# FMC_HPC_400.net
KiCad netlist of a schematic drawn in Altium Designer
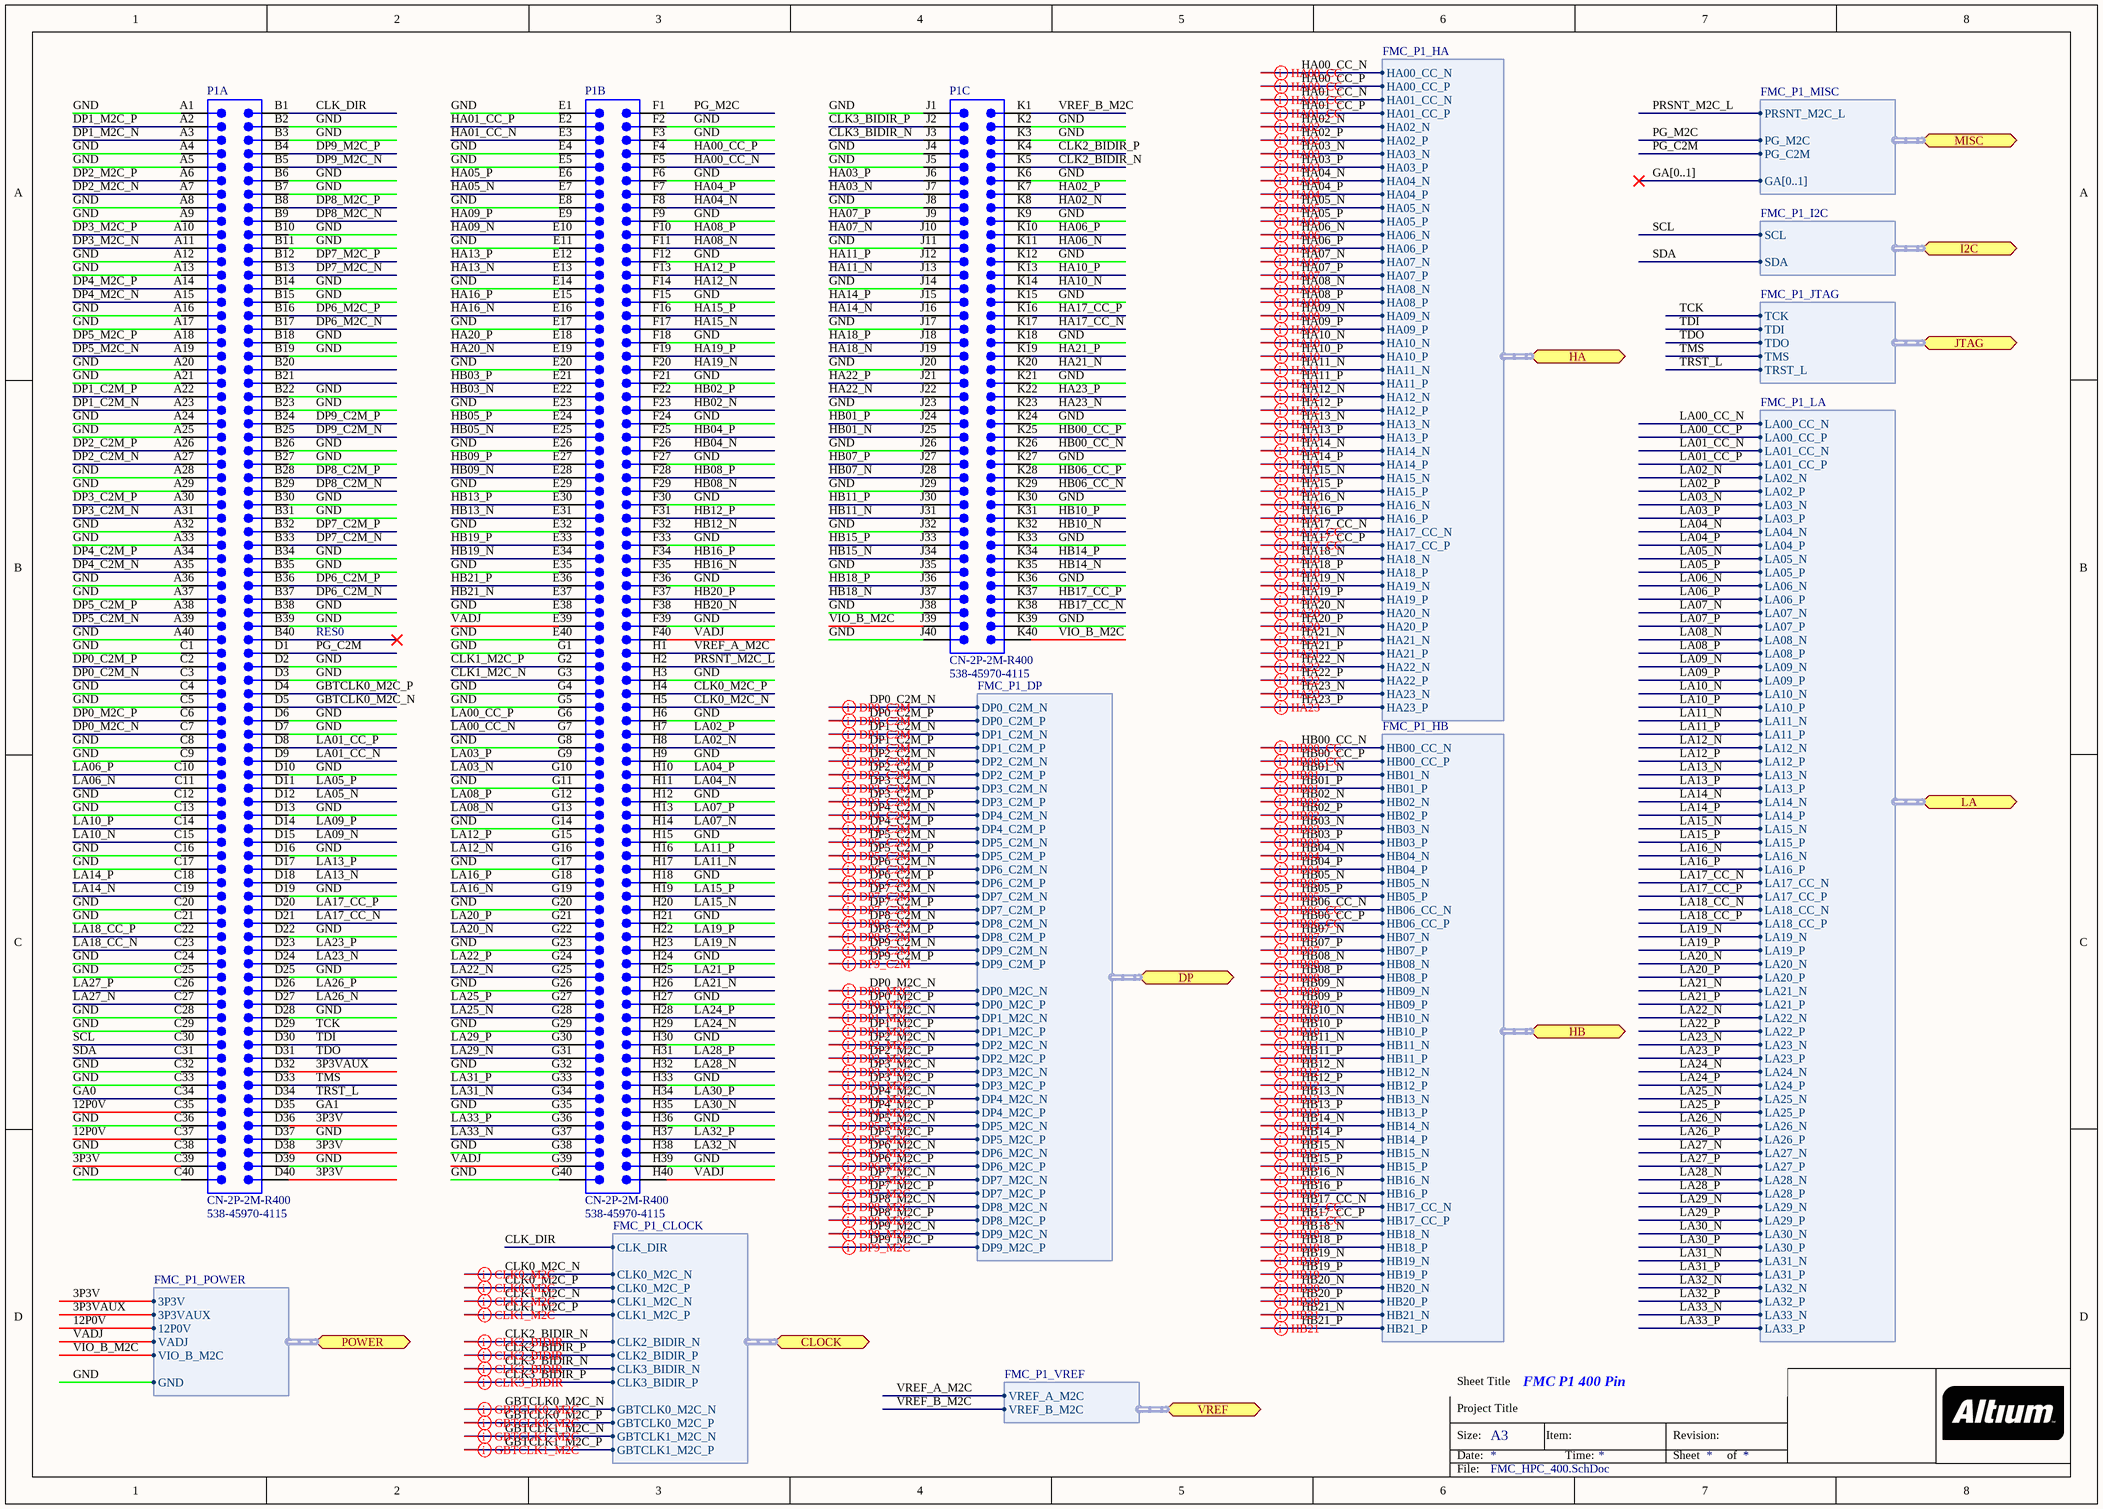
[diagram p0: FMC_HPC_400.SchDoc]

(export (version "E")
  (design (tool "Eeschema 10.0.6"))
  (components
    (comp (ref "P1")
      (value "CN-2P-2M-R400")
      (footprint "BTB-SM1-27-2V400M")
      (description "Board-to-Board Connector, Vertical, 10-Row, Pitch 1.27mm, 400-Position")
      (fields
        (field (name "MANUFACTURER") "Molex")
        (field (name "MANUFACTURER PART NUMBER") "45970-4115")
        (field (name "SUPPLIER PART NUMBER 1") "538-45970-4115")
      )
      (libsource (lib "RNG_Parts") (part "CN-2P-2M-R400"))
    )
  )
  (nets
    (net (code "11") (name "/3P3V") (class "Default")
      (node (ref "P1") (pin "C39") (pinfunction "C39_C39") (pintype "passive"))
      (node (ref "P1") (pin "D36") (pinfunction "D36_D36") (pintype "passive"))
      (node (ref "P1") (pin "D38") (pinfunction "D38_D38") (pintype "passive"))
      (node (ref "P1") (pin "D40") (pinfunction "D40_D40") (pintype "passive"))
    )
    (net (code "12") (name "/3P3VAUX") (class "Default")
      (node (ref "P1") (pin "D32") (pinfunction "D32_D32") (pintype "passive"))
    )
    (net (code "13") (name "/12P0V") (class "Default")
      (node (ref "P1") (pin "C35") (pinfunction "C35_C35") (pintype "passive"))
      (node (ref "P1") (pin "C37") (pinfunction "C37_C37") (pintype "passive"))
    )
    (net (code "14") (name "/CLK0_M2C_N") (class "Default")
      (node (ref "P1") (pin "H5") (pinfunction "H5_H5") (pintype "passive"))
    )
    (net (code "15") (name "/CLK0_M2C_P") (class "Default")
      (node (ref "P1") (pin "H4") (pinfunction "H4_H4") (pintype "passive"))
    )
    (net (code "16") (name "/CLK1_M2C_N") (class "Default")
      (node (ref "P1") (pin "G3") (pinfunction "G3_G3") (pintype "passive"))
    )
    (net (code "17") (name "/CLK1_M2C_P") (class "Default")
      (node (ref "P1") (pin "G2") (pinfunction "G2_G2") (pintype "passive"))
    )
    (net (code "18") (name "/CLK2_BIDIR_N") (class "Default")
      (node (ref "P1") (pin "K5") (pinfunction "K5_K5") (pintype "passive"))
    )
    (net (code "19") (name "/CLK2_BIDIR_P") (class "Default")
      (node (ref "P1") (pin "K4") (pinfunction "K4_K4") (pintype "passive"))
    )
    (net (code "20") (name "/CLK3_BIDIR_N") (class "Default")
      (node (ref "P1") (pin "J3") (pinfunction "J3_J3") (pintype "passive"))
    )
    (net (code "21") (name "/CLK3_BIDIR_P") (class "Default")
      (node (ref "P1") (pin "J2") (pinfunction "J2_J2") (pintype "passive"))
    )
    (net (code "22") (name "/CLK_DIR") (class "Default")
      (node (ref "P1") (pin "B1") (pinfunction "B1_B1") (pintype "passive"))
    )
    (net (code "23") (name "/DP0_C2M_N") (class "Default")
      (node (ref "P1") (pin "C3") (pinfunction "C3_C3") (pintype "passive"))
    )
    (net (code "24") (name "/DP0_C2M_P") (class "Default")
      (node (ref "P1") (pin "C2") (pinfunction "C2_C2") (pintype "passive"))
    )
    (net (code "25") (name "/DP0_M2C_N") (class "Default")
      (node (ref "P1") (pin "C7") (pinfunction "C7_C7") (pintype "passive"))
    )
    (net (code "26") (name "/DP0_M2C_P") (class "Default")
      (node (ref "P1") (pin "C6") (pinfunction "C6_C6") (pintype "passive"))
    )
    (net (code "27") (name "/DP1_C2M_N") (class "Default")
      (node (ref "P1") (pin "A23") (pinfunction "A23_A23") (pintype "passive"))
    )
    (net (code "28") (name "/DP1_C2M_P") (class "Default")
      (node (ref "P1") (pin "A22") (pinfunction "A22_A22") (pintype "passive"))
    )
    (net (code "29") (name "/DP1_M2C_N") (class "Default")
      (node (ref "P1") (pin "A3") (pinfunction "A3_A3") (pintype "passive"))
    )
    (net (code "30") (name "/DP1_M2C_P") (class "Default")
      (node (ref "P1") (pin "A2") (pinfunction "A2_A2") (pintype "passive"))
    )
    (net (code "31") (name "/DP2_C2M_N") (class "Default")
      (node (ref "P1") (pin "A27") (pinfunction "A27_A27") (pintype "passive"))
    )
    (net (code "32") (name "/DP2_C2M_P") (class "Default")
      (node (ref "P1") (pin "A26") (pinfunction "A26_A26") (pintype "passive"))
    )
    (net (code "33") (name "/DP2_M2C_N") (class "Default")
      (node (ref "P1") (pin "A7") (pinfunction "A7_A7") (pintype "passive"))
    )
    (net (code "34") (name "/DP2_M2C_P") (class "Default")
      (node (ref "P1") (pin "A6") (pinfunction "A6_A6") (pintype "passive"))
    )
    (net (code "35") (name "/DP3_C2M_N") (class "Default")
      (node (ref "P1") (pin "A31") (pinfunction "A31_A31") (pintype "passive"))
    )
    (net (code "36") (name "/DP3_C2M_P") (class "Default")
      (node (ref "P1") (pin "A30") (pinfunction "A30_A30") (pintype "passive"))
    )
    (net (code "37") (name "/DP3_M2C_N") (class "Default")
      (node (ref "P1") (pin "A11") (pinfunction "A11_A11") (pintype "passive"))
    )
    (net (code "38") (name "/DP3_M2C_P") (class "Default")
      (node (ref "P1") (pin "A10") (pinfunction "A10_A10") (pintype "passive"))
    )
    (net (code "39") (name "/DP4_C2M_N") (class "Default")
      (node (ref "P1") (pin "A35") (pinfunction "A35_A35") (pintype "passive"))
    )
    (net (code "40") (name "/DP4_C2M_P") (class "Default")
      (node (ref "P1") (pin "A34") (pinfunction "A34_A34") (pintype "passive"))
    )
    (net (code "41") (name "/DP4_M2C_N") (class "Default")
      (node (ref "P1") (pin "A15") (pinfunction "A15_A15") (pintype "passive"))
    )
    (net (code "42") (name "/DP4_M2C_P") (class "Default")
      (node (ref "P1") (pin "A14") (pinfunction "A14_A14") (pintype "passive"))
    )
    (net (code "43") (name "/DP5_C2M_N") (class "Default")
      (node (ref "P1") (pin "A39") (pinfunction "A39_A39") (pintype "passive"))
    )
    (net (code "44") (name "/DP5_C2M_P") (class "Default")
      (node (ref "P1") (pin "A38") (pinfunction "A38_A38") (pintype "passive"))
    )
    (net (code "45") (name "/DP5_M2C_N") (class "Default")
      (node (ref "P1") (pin "A19") (pinfunction "A19_A19") (pintype "passive"))
    )
    (net (code "46") (name "/DP5_M2C_P") (class "Default")
      (node (ref "P1") (pin "A18") (pinfunction "A18_A18") (pintype "passive"))
    )
    (net (code "47") (name "/DP6_C2M_N") (class "Default")
      (node (ref "P1") (pin "B37") (pinfunction "B37_B37") (pintype "passive"))
    )
    (net (code "48") (name "/DP6_C2M_P") (class "Default")
      (node (ref "P1") (pin "B36") (pinfunction "B36_B36") (pintype "passive"))
    )
    (net (code "49") (name "/DP6_M2C_N") (class "Default")
      (node (ref "P1") (pin "B17") (pinfunction "B17_B17") (pintype "passive"))
    )
    (net (code "50") (name "/DP6_M2C_P") (class "Default")
      (node (ref "P1") (pin "B16") (pinfunction "B16_B16") (pintype "passive"))
    )
    (net (code "51") (name "/DP7_C2M_N") (class "Default")
      (node (ref "P1") (pin "B33") (pinfunction "B33_B33") (pintype "passive"))
    )
    (net (code "52") (name "/DP7_C2M_P") (class "Default")
      (node (ref "P1") (pin "B32") (pinfunction "B32_B32") (pintype "passive"))
    )
    (net (code "53") (name "/DP7_M2C_N") (class "Default")
      (node (ref "P1") (pin "B13") (pinfunction "B13_B13") (pintype "passive"))
    )
    (net (code "54") (name "/DP7_M2C_P") (class "Default")
      (node (ref "P1") (pin "B12") (pinfunction "B12_B12") (pintype "passive"))
    )
    (net (code "55") (name "/DP8_C2M_N") (class "Default")
      (node (ref "P1") (pin "B29") (pinfunction "B29_B29") (pintype "passive"))
    )
    (net (code "56") (name "/DP8_C2M_P") (class "Default")
      (node (ref "P1") (pin "B28") (pinfunction "B28_B28") (pintype "passive"))
    )
    (net (code "57") (name "/DP8_M2C_N") (class "Default")
      (node (ref "P1") (pin "B9") (pinfunction "B9_B9") (pintype "passive"))
    )
    (net (code "58") (name "/DP8_M2C_P") (class "Default")
      (node (ref "P1") (pin "B8") (pinfunction "B8_B8") (pintype "passive"))
    )
    (net (code "59") (name "/DP9_C2M_N") (class "Default")
      (node (ref "P1") (pin "B25") (pinfunction "B25_B25") (pintype "passive"))
    )
    (net (code "60") (name "/DP9_C2M_P") (class "Default")
      (node (ref "P1") (pin "B24") (pinfunction "B24_B24") (pintype "passive"))
    )
    (net (code "61") (name "/DP9_M2C_N") (class "Default")
      (node (ref "P1") (pin "B5") (pinfunction "B5_B5") (pintype "passive"))
    )
    (net (code "62") (name "/DP9_M2C_P") (class "Default")
      (node (ref "P1") (pin "B4") (pinfunction "B4_B4") (pintype "passive"))
    )
    (net (code "63") (name "/GA0") (class "Default")
      (node (ref "P1") (pin "C34") (pinfunction "C34_C34") (pintype "passive"))
    )
    (net (code "64") (name "/GA1") (class "Default")
      (node (ref "P1") (pin "D35") (pinfunction "D35_D35") (pintype "passive"))
    )
    (net (code "65") (name "/GBTCLK0_M2C_N") (class "Default")
      (node (ref "P1") (pin "D5") (pinfunction "D5_D5") (pintype "passive"))
    )
    (net (code "66") (name "/GBTCLK0_M2C_P") (class "Default")
      (node (ref "P1") (pin "D4") (pinfunction "D4_D4") (pintype "passive"))
    )
    (net (code "69") (name "/GND") (class "Default")
      (node (ref "P1") (pin "A1") (pinfunction "A1_A1") (pintype "passive"))
      (node (ref "P1") (pin "A12") (pinfunction "A12_A12") (pintype "passive"))
      (node (ref "P1") (pin "A13") (pinfunction "A13_A13") (pintype "passive"))
      (node (ref "P1") (pin "A16") (pinfunction "A16_A16") (pintype "passive"))
      (node (ref "P1") (pin "A17") (pinfunction "A17_A17") (pintype "passive"))
      (node (ref "P1") (pin "A20") (pinfunction "A20_A20") (pintype "passive"))
      (node (ref "P1") (pin "A21") (pinfunction "A21_A21") (pintype "passive"))
      (node (ref "P1") (pin "A24") (pinfunction "A24_A24") (pintype "passive"))
      (node (ref "P1") (pin "A25") (pinfunction "A25_A25") (pintype "passive"))
      (node (ref "P1") (pin "A28") (pinfunction "A28_A28") (pintype "passive"))
      (node (ref "P1") (pin "A29") (pinfunction "A29_A29") (pintype "passive"))
      (node (ref "P1") (pin "A32") (pinfunction "A32_A32") (pintype "passive"))
      (node (ref "P1") (pin "A33") (pinfunction "A33_A33") (pintype "passive"))
      (node (ref "P1") (pin "A36") (pinfunction "A36_A36") (pintype "passive"))
      (node (ref "P1") (pin "A37") (pinfunction "A37_A37") (pintype "passive"))
      (node (ref "P1") (pin "A4") (pinfunction "A4_A4") (pintype "passive"))
      (node (ref "P1") (pin "A40") (pinfunction "A40_A40") (pintype "passive"))
      (node (ref "P1") (pin "A5") (pinfunction "A5_A5") (pintype "passive"))
      (node (ref "P1") (pin "A8") (pinfunction "A8_A8") (pintype "passive"))
      (node (ref "P1") (pin "A9") (pinfunction "A9_A9") (pintype "passive"))
      (node (ref "P1") (pin "B10") (pinfunction "B10_B10") (pintype "passive"))
      (node (ref "P1") (pin "B11") (pinfunction "B11_B11") (pintype "passive"))
      (node (ref "P1") (pin "B14") (pinfunction "B14_B14") (pintype "passive"))
      (node (ref "P1") (pin "B15") (pinfunction "B15_B15") (pintype "passive"))
      (node (ref "P1") (pin "B18") (pinfunction "B18_B18") (pintype "passive"))
      (node (ref "P1") (pin "B19") (pinfunction "B19_B19") (pintype "passive"))
      (node (ref "P1") (pin "B2") (pinfunction "B2_B2") (pintype "passive"))
      (node (ref "P1") (pin "B22") (pinfunction "B22_B22") (pintype "passive"))
      (node (ref "P1") (pin "B23") (pinfunction "B23_B23") (pintype "passive"))
      (node (ref "P1") (pin "B26") (pinfunction "B26_B26") (pintype "passive"))
      (node (ref "P1") (pin "B27") (pinfunction "B27_B27") (pintype "passive"))
      (node (ref "P1") (pin "B3") (pinfunction "B3_B3") (pintype "passive"))
      (node (ref "P1") (pin "B30") (pinfunction "B30_B30") (pintype "passive"))
      (node (ref "P1") (pin "B31") (pinfunction "B31_B31") (pintype "passive"))
      (node (ref "P1") (pin "B34") (pinfunction "B34_B34") (pintype "passive"))
      (node (ref "P1") (pin "B35") (pinfunction "B35_B35") (pintype "passive"))
      (node (ref "P1") (pin "B38") (pinfunction "B38_B38") (pintype "passive"))
      (node (ref "P1") (pin "B39") (pinfunction "B39_B39") (pintype "passive"))
      (node (ref "P1") (pin "B6") (pinfunction "B6_B6") (pintype "passive"))
      (node (ref "P1") (pin "B7") (pinfunction "B7_B7") (pintype "passive"))
      (node (ref "P1") (pin "C1") (pinfunction "C1_C1") (pintype "passive"))
      (node (ref "P1") (pin "C12") (pinfunction "C12_C12") (pintype "passive"))
      (node (ref "P1") (pin "C13") (pinfunction "C13_C13") (pintype "passive"))
      (node (ref "P1") (pin "C16") (pinfunction "C16_C16") (pintype "passive"))
      (node (ref "P1") (pin "C17") (pinfunction "C17_C17") (pintype "passive"))
      (node (ref "P1") (pin "C20") (pinfunction "C20_C20") (pintype "passive"))
      (node (ref "P1") (pin "C21") (pinfunction "C21_C21") (pintype "passive"))
      (node (ref "P1") (pin "C24") (pinfunction "C24_C24") (pintype "passive"))
      (node (ref "P1") (pin "C25") (pinfunction "C25_C25") (pintype "passive"))
      (node (ref "P1") (pin "C28") (pinfunction "C28_C28") (pintype "passive"))
      (node (ref "P1") (pin "C29") (pinfunction "C29_C29") (pintype "passive"))
      (node (ref "P1") (pin "C32") (pinfunction "C32_C32") (pintype "passive"))
      (node (ref "P1") (pin "C33") (pinfunction "C33_C33") (pintype "passive"))
      (node (ref "P1") (pin "C36") (pinfunction "C36_C36") (pintype "passive"))
      (node (ref "P1") (pin "C38") (pinfunction "C38_C38") (pintype "passive"))
      (node (ref "P1") (pin "C4") (pinfunction "C4_C4") (pintype "passive"))
      (node (ref "P1") (pin "C40") (pinfunction "C40_C40") (pintype "passive"))
      (node (ref "P1") (pin "C5") (pinfunction "C5_C5") (pintype "passive"))
      (node (ref "P1") (pin "C8") (pinfunction "C8_C8") (pintype "passive"))
      (node (ref "P1") (pin "C9") (pinfunction "C9_C9") (pintype "passive"))
      (node (ref "P1") (pin "D10") (pinfunction "D10_D10") (pintype "passive"))
      (node (ref "P1") (pin "D13") (pinfunction "D13_D13") (pintype "passive"))
      (node (ref "P1") (pin "D16") (pinfunction "D16_D16") (pintype "passive"))
      (node (ref "P1") (pin "D19") (pinfunction "D19_D19") (pintype "passive"))
      (node (ref "P1") (pin "D2") (pinfunction "D2_D2") (pintype "passive"))
      (node (ref "P1") (pin "D22") (pinfunction "D22_D22") (pintype "passive"))
      (node (ref "P1") (pin "D25") (pinfunction "D25_D25") (pintype "passive"))
      (node (ref "P1") (pin "D28") (pinfunction "D28_D28") (pintype "passive"))
      (node (ref "P1") (pin "D3") (pinfunction "D3_D3") (pintype "passive"))
      (node (ref "P1") (pin "D37") (pinfunction "D37_D37") (pintype "passive"))
      (node (ref "P1") (pin "D39") (pinfunction "D39_D39") (pintype "passive"))
      (node (ref "P1") (pin "D6") (pinfunction "D6_D6") (pintype "passive"))
      (node (ref "P1") (pin "D7") (pinfunction "D7_D7") (pintype "passive"))
      (node (ref "P1") (pin "E1") (pinfunction "E1_E1") (pintype "passive"))
      (node (ref "P1") (pin "E11") (pinfunction "E11_E11") (pintype "passive"))
      (node (ref "P1") (pin "E14") (pinfunction "E14_E14") (pintype "passive"))
      (node (ref "P1") (pin "E17") (pinfunction "E17_E17") (pintype "passive"))
      (node (ref "P1") (pin "E20") (pinfunction "E20_E20") (pintype "passive"))
      (node (ref "P1") (pin "E23") (pinfunction "E23_E23") (pintype "passive"))
      (node (ref "P1") (pin "E26") (pinfunction "E26_E26") (pintype "passive"))
      (node (ref "P1") (pin "E29") (pinfunction "E29_E29") (pintype "passive"))
      (node (ref "P1") (pin "E32") (pinfunction "E32_E32") (pintype "passive"))
      (node (ref "P1") (pin "E35") (pinfunction "E35_E35") (pintype "passive"))
      (node (ref "P1") (pin "E38") (pinfunction "E38_E38") (pintype "passive"))
      (node (ref "P1") (pin "E4") (pinfunction "E4_E4") (pintype "passive"))
      (node (ref "P1") (pin "E40") (pinfunction "E40_E40") (pintype "passive"))
      (node (ref "P1") (pin "E5") (pinfunction "E5_E5") (pintype "passive"))
      (node (ref "P1") (pin "E8") (pinfunction "E8_E8") (pintype "passive"))
      (node (ref "P1") (pin "F12") (pinfunction "F12_F12") (pintype "passive"))
      (node (ref "P1") (pin "F15") (pinfunction "F15_F15") (pintype "passive"))
      (node (ref "P1") (pin "F18") (pinfunction "F18_F18") (pintype "passive"))
      (node (ref "P1") (pin "F2") (pinfunction "F2_F2") (pintype "passive"))
      (node (ref "P1") (pin "F21") (pinfunction "F21_F21") (pintype "passive"))
      (node (ref "P1") (pin "F24") (pinfunction "F24_F24") (pintype "passive"))
      (node (ref "P1") (pin "F27") (pinfunction "F27_F27") (pintype "passive"))
      (node (ref "P1") (pin "F3") (pinfunction "F3_F3") (pintype "passive"))
      (node (ref "P1") (pin "F30") (pinfunction "F30_F30") (pintype "passive"))
      (node (ref "P1") (pin "F33") (pinfunction "F33_F33") (pintype "passive"))
      (node (ref "P1") (pin "F36") (pinfunction "F36_F36") (pintype "passive"))
      (node (ref "P1") (pin "F39") (pinfunction "F39_F39") (pintype "passive"))
      (node (ref "P1") (pin "F6") (pinfunction "F6_F6") (pintype "passive"))
      (node (ref "P1") (pin "F9") (pinfunction "F9_F9") (pintype "passive"))
      (node (ref "P1") (pin "G1") (pinfunction "G1_G1") (pintype "passive"))
      (node (ref "P1") (pin "G11") (pinfunction "G11_G11") (pintype "passive"))
      (node (ref "P1") (pin "G14") (pinfunction "G14_G14") (pintype "passive"))
      (node (ref "P1") (pin "G17") (pinfunction "G17_G17") (pintype "passive"))
      (node (ref "P1") (pin "G20") (pinfunction "G20_G20") (pintype "passive"))
      (node (ref "P1") (pin "G23") (pinfunction "G23_G23") (pintype "passive"))
      (node (ref "P1") (pin "G26") (pinfunction "G26_G26") (pintype "passive"))
      (node (ref "P1") (pin "G29") (pinfunction "G29_G29") (pintype "passive"))
      (node (ref "P1") (pin "G32") (pinfunction "G32_G32") (pintype "passive"))
      (node (ref "P1") (pin "G35") (pinfunction "G35_G35") (pintype "passive"))
      (node (ref "P1") (pin "G38") (pinfunction "G38_G38") (pintype "passive"))
      (node (ref "P1") (pin "G4") (pinfunction "G4_G4") (pintype "passive"))
      (node (ref "P1") (pin "G40") (pinfunction "G40_G40") (pintype "passive"))
      (node (ref "P1") (pin "G5") (pinfunction "G5_G5") (pintype "passive"))
      (node (ref "P1") (pin "G8") (pinfunction "G8_G8") (pintype "passive"))
      (node (ref "P1") (pin "H12") (pinfunction "H12_H12") (pintype "passive"))
      (node (ref "P1") (pin "H15") (pinfunction "H15_H15") (pintype "passive"))
      (node (ref "P1") (pin "H18") (pinfunction "H18_H18") (pintype "passive"))
      (node (ref "P1") (pin "H21") (pinfunction "H21_H21") (pintype "passive"))
      (node (ref "P1") (pin "H24") (pinfunction "H24_H24") (pintype "passive"))
      (node (ref "P1") (pin "H27") (pinfunction "H27_H27") (pintype "passive"))
      (node (ref "P1") (pin "H3") (pinfunction "H3_H3") (pintype "passive"))
      (node (ref "P1") (pin "H30") (pinfunction "H30_H30") (pintype "passive"))
      (node (ref "P1") (pin "H33") (pinfunction "H33_H33") (pintype "passive"))
      (node (ref "P1") (pin "H36") (pinfunction "H36_H36") (pintype "passive"))
      (node (ref "P1") (pin "H39") (pinfunction "H39_H39") (pintype "passive"))
      (node (ref "P1") (pin "H6") (pinfunction "H6_H6") (pintype "passive"))
      (node (ref "P1") (pin "H9") (pinfunction "H9_H9") (pintype "passive"))
      (node (ref "P1") (pin "J1") (pinfunction "J1_J1") (pintype "passive"))
      (node (ref "P1") (pin "J11") (pinfunction "J11_J11") (pintype "passive"))
      (node (ref "P1") (pin "J14") (pinfunction "J14_J14") (pintype "passive"))
      (node (ref "P1") (pin "J17") (pinfunction "J17_J17") (pintype "passive"))
      (node (ref "P1") (pin "J20") (pinfunction "J20_J20") (pintype "passive"))
      (node (ref "P1") (pin "J23") (pinfunction "J23_J23") (pintype "passive"))
      (node (ref "P1") (pin "J26") (pinfunction "J26_J26") (pintype "passive"))
      (node (ref "P1") (pin "J29") (pinfunction "J29_J29") (pintype "passive"))
      (node (ref "P1") (pin "J32") (pinfunction "J32_J32") (pintype "passive"))
      (node (ref "P1") (pin "J35") (pinfunction "J35_J35") (pintype "passive"))
      (node (ref "P1") (pin "J38") (pinfunction "J38_J38") (pintype "passive"))
      (node (ref "P1") (pin "J4") (pinfunction "J4_J4") (pintype "passive"))
      (node (ref "P1") (pin "J40") (pinfunction "J40_J40") (pintype "passive"))
      (node (ref "P1") (pin "J5") (pinfunction "J5_J5") (pintype "passive"))
      (node (ref "P1") (pin "J8") (pinfunction "J8_J8") (pintype "passive"))
      (node (ref "P1") (pin "K12") (pinfunction "K12_K12") (pintype "passive"))
      (node (ref "P1") (pin "K15") (pinfunction "K15_K15") (pintype "passive"))
      (node (ref "P1") (pin "K18") (pinfunction "K18_K18") (pintype "passive"))
      (node (ref "P1") (pin "K2") (pinfunction "K2_K2") (pintype "passive"))
      (node (ref "P1") (pin "K21") (pinfunction "K21_K21") (pintype "passive"))
      (node (ref "P1") (pin "K24") (pinfunction "K24_K24") (pintype "passive"))
      (node (ref "P1") (pin "K27") (pinfunction "K27_K27") (pintype "passive"))
      (node (ref "P1") (pin "K3") (pinfunction "K3_K3") (pintype "passive"))
      (node (ref "P1") (pin "K30") (pinfunction "K30_K30") (pintype "passive"))
      (node (ref "P1") (pin "K33") (pinfunction "K33_K33") (pintype "passive"))
      (node (ref "P1") (pin "K36") (pinfunction "K36_K36") (pintype "passive"))
      (node (ref "P1") (pin "K39") (pinfunction "K39_K39") (pintype "passive"))
      (node (ref "P1") (pin "K6") (pinfunction "K6_K6") (pintype "passive"))
      (node (ref "P1") (pin "K9") (pinfunction "K9_K9") (pintype "passive"))
    )
    (net (code "70") (name "/HA00_CC_N") (class "Default")
      (node (ref "P1") (pin "F5") (pinfunction "F5_F5") (pintype "passive"))
    )
    (net (code "71") (name "/HA00_CC_P") (class "Default")
      (node (ref "P1") (pin "F4") (pinfunction "F4_F4") (pintype "passive"))
    )
    (net (code "72") (name "/HA01_CC_N") (class "Default")
      (node (ref "P1") (pin "E3") (pinfunction "E3_E3") (pintype "passive"))
    )
    (net (code "73") (name "/HA01_CC_P") (class "Default")
      (node (ref "P1") (pin "E2") (pinfunction "E2_E2") (pintype "passive"))
    )
    (net (code "74") (name "/HA02_N") (class "Default")
      (node (ref "P1") (pin "K8") (pinfunction "K8_K8") (pintype "passive"))
    )
    (net (code "75") (name "/HA02_P") (class "Default")
      (node (ref "P1") (pin "K7") (pinfunction "K7_K7") (pintype "passive"))
    )
    (net (code "76") (name "/HA03_N") (class "Default")
      (node (ref "P1") (pin "J7") (pinfunction "J7_J7") (pintype "passive"))
    )
    (net (code "77") (name "/HA03_P") (class "Default")
      (node (ref "P1") (pin "J6") (pinfunction "J6_J6") (pintype "passive"))
    )
    (net (code "78") (name "/HA04_N") (class "Default")
      (node (ref "P1") (pin "F8") (pinfunction "F8_F8") (pintype "passive"))
    )
    (net (code "79") (name "/HA04_P") (class "Default")
      (node (ref "P1") (pin "F7") (pinfunction "F7_F7") (pintype "passive"))
    )
    (net (code "80") (name "/HA05_N") (class "Default")
      (node (ref "P1") (pin "E7") (pinfunction "E7_E7") (pintype "passive"))
    )
    (net (code "81") (name "/HA05_P") (class "Default")
      (node (ref "P1") (pin "E6") (pinfunction "E6_E6") (pintype "passive"))
    )
    (net (code "82") (name "/HA06_N") (class "Default")
      (node (ref "P1") (pin "K11") (pinfunction "K11_K11") (pintype "passive"))
    )
    (net (code "83") (name "/HA06_P") (class "Default")
      (node (ref "P1") (pin "K10") (pinfunction "K10_K10") (pintype "passive"))
    )
    (net (code "84") (name "/HA07_N") (class "Default")
      (node (ref "P1") (pin "J10") (pinfunction "J10_J10") (pintype "passive"))
    )
    (net (code "85") (name "/HA07_P") (class "Default")
      (node (ref "P1") (pin "J9") (pinfunction "J9_J9") (pintype "passive"))
    )
    (net (code "86") (name "/HA08_N") (class "Default")
      (node (ref "P1") (pin "F11") (pinfunction "F11_F11") (pintype "passive"))
    )
    (net (code "87") (name "/HA08_P") (class "Default")
      (node (ref "P1") (pin "F10") (pinfunction "F10_F10") (pintype "passive"))
    )
    (net (code "88") (name "/HA09_N") (class "Default")
      (node (ref "P1") (pin "E10") (pinfunction "E10_E10") (pintype "passive"))
    )
    (net (code "89") (name "/HA09_P") (class "Default")
      (node (ref "P1") (pin "E9") (pinfunction "E9_E9") (pintype "passive"))
    )
    (net (code "90") (name "/HA10_N") (class "Default")
      (node (ref "P1") (pin "K14") (pinfunction "K14_K14") (pintype "passive"))
    )
    (net (code "91") (name "/HA10_P") (class "Default")
      (node (ref "P1") (pin "K13") (pinfunction "K13_K13") (pintype "passive"))
    )
    (net (code "92") (name "/HA11_N") (class "Default")
      (node (ref "P1") (pin "J13") (pinfunction "J13_J13") (pintype "passive"))
    )
    (net (code "93") (name "/HA11_P") (class "Default")
      (node (ref "P1") (pin "J12") (pinfunction "J12_J12") (pintype "passive"))
    )
    (net (code "94") (name "/HA12_N") (class "Default")
      (node (ref "P1") (pin "F14") (pinfunction "F14_F14") (pintype "passive"))
    )
    (net (code "95") (name "/HA12_P") (class "Default")
      (node (ref "P1") (pin "F13") (pinfunction "F13_F13") (pintype "passive"))
    )
    (net (code "96") (name "/HA13_N") (class "Default")
      (node (ref "P1") (pin "E13") (pinfunction "E13_E13") (pintype "passive"))
    )
    (net (code "97") (name "/HA13_P") (class "Default")
      (node (ref "P1") (pin "E12") (pinfunction "E12_E12") (pintype "passive"))
    )
    (net (code "98") (name "/HA14_N") (class "Default")
      (node (ref "P1") (pin "J16") (pinfunction "J16_J16") (pintype "passive"))
    )
    (net (code "99") (name "/HA14_P") (class "Default")
      (node (ref "P1") (pin "J15") (pinfunction "J15_J15") (pintype "passive"))
    )
    (net (code "100") (name "/HA15_N") (class "Default")
      (node (ref "P1") (pin "F17") (pinfunction "F17_F17") (pintype "passive"))
    )
    (net (code "101") (name "/HA15_P") (class "Default")
      (node (ref "P1") (pin "F16") (pinfunction "F16_F16") (pintype "passive"))
    )
    (net (code "102") (name "/HA16_N") (class "Default")
      (node (ref "P1") (pin "E16") (pinfunction "E16_E16") (pintype "passive"))
    )
    (net (code "103") (name "/HA16_P") (class "Default")
      (node (ref "P1") (pin "E15") (pinfunction "E15_E15") (pintype "passive"))
    )
    (net (code "104") (name "/HA17_CC_N") (class "Default")
      (node (ref "P1") (pin "K17") (pinfunction "K17_K17") (pintype "passive"))
    )
    (net (code "105") (name "/HA17_CC_P") (class "Default")
      (node (ref "P1") (pin "K16") (pinfunction "K16_K16") (pintype "passive"))
    )
    (net (code "106") (name "/HA18_N") (class "Default")
      (node (ref "P1") (pin "J19") (pinfunction "J19_J19") (pintype "passive"))
    )
    (net (code "107") (name "/HA18_P") (class "Default")
      (node (ref "P1") (pin "J18") (pinfunction "J18_J18") (pintype "passive"))
    )
    (net (code "108") (name "/HA19_N") (class "Default")
      (node (ref "P1") (pin "F20") (pinfunction "F20_F20") (pintype "passive"))
    )
    (net (code "109") (name "/HA19_P") (class "Default")
      (node (ref "P1") (pin "F19") (pinfunction "F19_F19") (pintype "passive"))
    )
    (net (code "110") (name "/HA20_N") (class "Default")
      (node (ref "P1") (pin "E19") (pinfunction "E19_E19") (pintype "passive"))
    )
    (net (code "111") (name "/HA20_P") (class "Default")
      (node (ref "P1") (pin "E18") (pinfunction "E18_E18") (pintype "passive"))
    )
    (net (code "112") (name "/HA21_N") (class "Default")
      (node (ref "P1") (pin "K20") (pinfunction "K20_K20") (pintype "passive"))
    )
    (net (code "113") (name "/HA21_P") (class "Default")
      (node (ref "P1") (pin "K19") (pinfunction "K19_K19") (pintype "passive"))
    )
    (net (code "114") (name "/HA22_N") (class "Default")
      (node (ref "P1") (pin "J22") (pinfunction "J22_J22") (pintype "passive"))
    )
    (net (code "115") (name "/HA22_P") (class "Default")
      (node (ref "P1") (pin "J21") (pinfunction "J21_J21") (pintype "passive"))
    )
    (net (code "116") (name "/HA23_N") (class "Default")
      (node (ref "P1") (pin "K23") (pinfunction "K23_K23") (pintype "passive"))
    )
    (net (code "117") (name "/HA23_P") (class "Default")
      (node (ref "P1") (pin "K22") (pinfunction "K22_K22") (pintype "passive"))
    )
    (net (code "118") (name "/HB00_CC_N") (class "Default")
      (node (ref "P1") (pin "K26") (pinfunction "K26_K26") (pintype "passive"))
    )
    (net (code "119") (name "/HB00_CC_P") (class "Default")
      (node (ref "P1") (pin "K25") (pinfunction "K25_K25") (pintype "passive"))
    )
    (net (code "120") (name "/HB01_N") (class "Default")
      (node (ref "P1") (pin "J25") (pinfunction "J25_J25") (pintype "passive"))
    )
    (net (code "121") (name "/HB01_P") (class "Default")
      (node (ref "P1") (pin "J24") (pinfunction "J24_J24") (pintype "passive"))
    )
    (net (code "122") (name "/HB02_N") (class "Default")
      (node (ref "P1") (pin "F23") (pinfunction "F23_F23") (pintype "passive"))
    )
    (net (code "123") (name "/HB02_P") (class "Default")
      (node (ref "P1") (pin "F22") (pinfunction "F22_F22") (pintype "passive"))
    )
    (net (code "124") (name "/HB03_N") (class "Default")
      (node (ref "P1") (pin "E22") (pinfunction "E22_E22") (pintype "passive"))
    )
    (net (code "125") (name "/HB03_P") (class "Default")
      (node (ref "P1") (pin "E21") (pinfunction "E21_E21") (pintype "passive"))
    )
    (net (code "126") (name "/HB04_N") (class "Default")
      (node (ref "P1") (pin "F26") (pinfunction "F26_F26") (pintype "passive"))
    )
    (net (code "127") (name "/HB04_P") (class "Default")
      (node (ref "P1") (pin "F25") (pinfunction "F25_F25") (pintype "passive"))
    )
    (net (code "128") (name "/HB05_N") (class "Default")
      (node (ref "P1") (pin "E25") (pinfunction "E25_E25") (pintype "passive"))
    )
    (net (code "129") (name "/HB05_P") (class "Default")
      (node (ref "P1") (pin "E24") (pinfunction "E24_E24") (pintype "passive"))
    )
    (net (code "130") (name "/HB06_CC_N") (class "Default")
      (node (ref "P1") (pin "K29") (pinfunction "K29_K29") (pintype "passive"))
    )
    (net (code "131") (name "/HB06_CC_P") (class "Default")
      (node (ref "P1") (pin "K28") (pinfunction "K28_K28") (pintype "passive"))
    )
    (net (code "132") (name "/HB07_N") (class "Default")
      (node (ref "P1") (pin "J28") (pinfunction "J28_J28") (pintype "passive"))
    )
    (net (code "133") (name "/HB07_P") (class "Default")
      (node (ref "P1") (pin "J27") (pinfunction "J27_J27") (pintype "passive"))
    )
    (net (code "134") (name "/HB08_N") (class "Default")
      (node (ref "P1") (pin "F29") (pinfunction "F29_F29") (pintype "passive"))
    )
    (net (code "135") (name "/HB08_P") (class "Default")
      (node (ref "P1") (pin "F28") (pinfunction "F28_F28") (pintype "passive"))
    )
    (net (code "136") (name "/HB09_N") (class "Default")
      (node (ref "P1") (pin "E28") (pinfunction "E28_E28") (pintype "passive"))
    )
    (net (code "137") (name "/HB09_P") (class "Default")
      (node (ref "P1") (pin "E27") (pinfunction "E27_E27") (pintype "passive"))
    )
    (net (code "138") (name "/HB10_N") (class "Default")
      (node (ref "P1") (pin "K32") (pinfunction "K32_K32") (pintype "passive"))
    )
    (net (code "139") (name "/HB10_P") (class "Default")
      (node (ref "P1") (pin "K31") (pinfunction "K31_K31") (pintype "passive"))
    )
    (net (code "140") (name "/HB11_N") (class "Default")
      (node (ref "P1") (pin "J31") (pinfunction "J31_J31") (pintype "passive"))
    )
    (net (code "141") (name "/HB11_P") (class "Default")
      (node (ref "P1") (pin "J30") (pinfunction "J30_J30") (pintype "passive"))
    )
    (net (code "142") (name "/HB12_N") (class "Default")
      (node (ref "P1") (pin "F32") (pinfunction "F32_F32") (pintype "passive"))
    )
    (net (code "143") (name "/HB12_P") (class "Default")
      (node (ref "P1") (pin "F31") (pinfunction "F31_F31") (pintype "passive"))
    )
    (net (code "144") (name "/HB13_N") (class "Default")
      (node (ref "P1") (pin "E31") (pinfunction "E31_E31") (pintype "passive"))
    )
    (net (code "145") (name "/HB13_P") (class "Default")
      (node (ref "P1") (pin "E30") (pinfunction "E30_E30") (pintype "passive"))
    )
    (net (code "146") (name "/HB14_N") (class "Default")
      (node (ref "P1") (pin "K35") (pinfunction "K35_K35") (pintype "passive"))
    )
    (net (code "147") (name "/HB14_P") (class "Default")
      (node (ref "P1") (pin "K34") (pinfunction "K34_K34") (pintype "passive"))
    )
    (net (code "148") (name "/HB15_N") (class "Default")
      (node (ref "P1") (pin "J34") (pinfunction "J34_J34") (pintype "passive"))
    )
    (net (code "149") (name "/HB15_P") (class "Default")
      (node (ref "P1") (pin "J33") (pinfunction "J33_J33") (pintype "passive"))
    )
    (net (code "150") (name "/HB16_N") (class "Default")
      (node (ref "P1") (pin "F35") (pinfunction "F35_F35") (pintype "passive"))
    )
    (net (code "151") (name "/HB16_P") (class "Default")
      (node (ref "P1") (pin "F34") (pinfunction "F34_F34") (pintype "passive"))
    )
    (net (code "152") (name "/HB17_CC_N") (class "Default")
      (node (ref "P1") (pin "K38") (pinfunction "K38_K38") (pintype "passive"))
    )
    (net (code "153") (name "/HB17_CC_P") (class "Default")
      (node (ref "P1") (pin "K37") (pinfunction "K37_K37") (pintype "passive"))
    )
    (net (code "154") (name "/HB18_N") (class "Default")
      (node (ref "P1") (pin "J37") (pinfunction "J37_J37") (pintype "passive"))
    )
    (net (code "155") (name "/HB18_P") (class "Default")
      (node (ref "P1") (pin "J36") (pinfunction "J36_J36") (pintype "passive"))
    )
    (net (code "156") (name "/HB19_N") (class "Default")
      (node (ref "P1") (pin "E34") (pinfunction "E34_E34") (pintype "passive"))
    )
    (net (code "157") (name "/HB19_P") (class "Default")
      (node (ref "P1") (pin "E33") (pinfunction "E33_E33") (pintype "passive"))
    )
    (net (code "158") (name "/HB20_N") (class "Default")
      (node (ref "P1") (pin "F38") (pinfunction "F38_F38") (pintype "passive"))
    )
    (net (code "159") (name "/HB20_P") (class "Default")
      (node (ref "P1") (pin "F37") (pinfunction "F37_F37") (pintype "passive"))
    )
    (net (code "160") (name "/HB21_N") (class "Default")
      (node (ref "P1") (pin "E37") (pinfunction "E37_E37") (pintype "passive"))
    )
    (net (code "161") (name "/HB21_P") (class "Default")
      (node (ref "P1") (pin "E36") (pinfunction "E36_E36") (pintype "passive"))
    )
    (net (code "162") (name "/LA00_CC_N") (class "Default")
      (node (ref "P1") (pin "G7") (pinfunction "G7_G7") (pintype "passive"))
    )
    (net (code "163") (name "/LA00_CC_P") (class "Default")
      (node (ref "P1") (pin "G6") (pinfunction "G6_G6") (pintype "passive"))
    )
    (net (code "164") (name "/LA01_CC_N") (class "Default")
      (node (ref "P1") (pin "D9") (pinfunction "D9_D9") (pintype "passive"))
    )
    (net (code "165") (name "/LA01_CC_P") (class "Default")
      (node (ref "P1") (pin "D8") (pinfunction "D8_D8") (pintype "passive"))
    )
    (net (code "166") (name "/LA02_N") (class "Default")
      (node (ref "P1") (pin "H8") (pinfunction "H8_H8") (pintype "passive"))
    )
    (net (code "167") (name "/LA02_P") (class "Default")
      (node (ref "P1") (pin "H7") (pinfunction "H7_H7") (pintype "passive"))
    )
    (net (code "168") (name "/LA03_N") (class "Default")
      (node (ref "P1") (pin "G10") (pinfunction "G10_G10") (pintype "passive"))
    )
    (net (code "169") (name "/LA03_P") (class "Default")
      (node (ref "P1") (pin "G9") (pinfunction "G9_G9") (pintype "passive"))
    )
    (net (code "170") (name "/LA04_N") (class "Default")
      (node (ref "P1") (pin "H11") (pinfunction "H11_H11") (pintype "passive"))
    )
    (net (code "171") (name "/LA04_P") (class "Default")
      (node (ref "P1") (pin "H10") (pinfunction "H10_H10") (pintype "passive"))
    )
    (net (code "172") (name "/LA05_N") (class "Default")
      (node (ref "P1") (pin "D12") (pinfunction "D12_D12") (pintype "passive"))
    )
    (net (code "173") (name "/LA05_P") (class "Default")
      (node (ref "P1") (pin "D11") (pinfunction "D11_D11") (pintype "passive"))
    )
    (net (code "174") (name "/LA06_N") (class "Default")
      (node (ref "P1") (pin "C11") (pinfunction "C11_C11") (pintype "passive"))
    )
    (net (code "175") (name "/LA06_P") (class "Default")
      (node (ref "P1") (pin "C10") (pinfunction "C10_C10") (pintype "passive"))
    )
    (net (code "176") (name "/LA07_N") (class "Default")
      (node (ref "P1") (pin "H14") (pinfunction "H14_H14") (pintype "passive"))
    )
    (net (code "177") (name "/LA07_P") (class "Default")
      (node (ref "P1") (pin "H13") (pinfunction "H13_H13") (pintype "passive"))
    )
    (net (code "178") (name "/LA08_N") (class "Default")
      (node (ref "P1") (pin "G13") (pinfunction "G13_G13") (pintype "passive"))
    )
    (net (code "179") (name "/LA08_P") (class "Default")
      (node (ref "P1") (pin "G12") (pinfunction "G12_G12") (pintype "passive"))
    )
    (net (code "180") (name "/LA09_N") (class "Default")
      (node (ref "P1") (pin "D15") (pinfunction "D15_D15") (pintype "passive"))
    )
    (net (code "181") (name "/LA09_P") (class "Default")
      (node (ref "P1") (pin "D14") (pinfunction "D14_D14") (pintype "passive"))
    )
    (net (code "182") (name "/LA10_N") (class "Default")
      (node (ref "P1") (pin "C15") (pinfunction "C15_C15") (pintype "passive"))
    )
    (net (code "183") (name "/LA10_P") (class "Default")
      (node (ref "P1") (pin "C14") (pinfunction "C14_C14") (pintype "passive"))
    )
    (net (code "184") (name "/LA11_N") (class "Default")
      (node (ref "P1") (pin "H17") (pinfunction "H17_H17") (pintype "passive"))
    )
    (net (code "185") (name "/LA11_P") (class "Default")
      (node (ref "P1") (pin "H16") (pinfunction "H16_H16") (pintype "passive"))
    )
    (net (code "186") (name "/LA12_N") (class "Default")
      (node (ref "P1") (pin "G16") (pinfunction "G16_G16") (pintype "passive"))
    )
    (net (code "187") (name "/LA12_P") (class "Default")
      (node (ref "P1") (pin "G15") (pinfunction "G15_G15") (pintype "passive"))
    )
    (net (code "188") (name "/LA13_N") (class "Default")
      (node (ref "P1") (pin "D18") (pinfunction "D18_D18") (pintype "passive"))
    )
    (net (code "189") (name "/LA13_P") (class "Default")
      (node (ref "P1") (pin "D17") (pinfunction "D17_D17") (pintype "passive"))
    )
    (net (code "190") (name "/LA14_N") (class "Default")
      (node (ref "P1") (pin "C19") (pinfunction "C19_C19") (pintype "passive"))
    )
    (net (code "191") (name "/LA14_P") (class "Default")
      (node (ref "P1") (pin "C18") (pinfunction "C18_C18") (pintype "passive"))
    )
    (net (code "192") (name "/LA15_N") (class "Default")
      (node (ref "P1") (pin "H20") (pinfunction "H20_H20") (pintype "passive"))
    )
    (net (code "193") (name "/LA15_P") (class "Default")
      (node (ref "P1") (pin "H19") (pinfunction "H19_H19") (pintype "passive"))
    )
    (net (code "194") (name "/LA16_N") (class "Default")
      (node (ref "P1") (pin "G19") (pinfunction "G19_G19") (pintype "passive"))
    )
    (net (code "195") (name "/LA16_P") (class "Default")
      (node (ref "P1") (pin "G18") (pinfunction "G18_G18") (pintype "passive"))
    )
    (net (code "196") (name "/LA17_CC_N") (class "Default")
      (node (ref "P1") (pin "D21") (pinfunction "D21_D21") (pintype "passive"))
    )
    (net (code "197") (name "/LA17_CC_P") (class "Default")
      (node (ref "P1") (pin "D20") (pinfunction "D20_D20") (pintype "passive"))
    )
    (net (code "198") (name "/LA18_CC_N") (class "Default")
      (node (ref "P1") (pin "C23") (pinfunction "C23_C23") (pintype "passive"))
    )
    (net (code "199") (name "/LA18_CC_P") (class "Default")
      (node (ref "P1") (pin "C22") (pinfunction "C22_C22") (pintype "passive"))
    )
    (net (code "200") (name "/LA19_N") (class "Default")
      (node (ref "P1") (pin "H23") (pinfunction "H23_H23") (pintype "passive"))
    )
    (net (code "201") (name "/LA19_P") (class "Default")
      (node (ref "P1") (pin "H22") (pinfunction "H22_H22") (pintype "passive"))
    )
    (net (code "202") (name "/LA20_N") (class "Default")
      (node (ref "P1") (pin "G22") (pinfunction "G22_G22") (pintype "passive"))
    )
    (net (code "203") (name "/LA20_P") (class "Default")
      (node (ref "P1") (pin "G21") (pinfunction "G21_G21") (pintype "passive"))
    )
    (net (code "204") (name "/LA21_N") (class "Default")
      (node (ref "P1") (pin "H26") (pinfunction "H26_H26") (pintype "passive"))
    )
    (net (code "205") (name "/LA21_P") (class "Default")
      (node (ref "P1") (pin "H25") (pinfunction "H25_H25") (pintype "passive"))
    )
    (net (code "206") (name "/LA22_N") (class "Default")
      (node (ref "P1") (pin "G25") (pinfunction "G25_G25") (pintype "passive"))
    )
    (net (code "207") (name "/LA22_P") (class "Default")
      (node (ref "P1") (pin "G24") (pinfunction "G24_G24") (pintype "passive"))
    )
    (net (code "208") (name "/LA23_N") (class "Default")
      (node (ref "P1") (pin "D24") (pinfunction "D24_D24") (pintype "passive"))
    )
    (net (code "209") (name "/LA23_P") (class "Default")
      (node (ref "P1") (pin "D23") (pinfunction "D23_D23") (pintype "passive"))
    )
    (net (code "210") (name "/LA24_N") (class "Default")
      (node (ref "P1") (pin "H29") (pinfunction "H29_H29") (pintype "passive"))
    )
    (net (code "211") (name "/LA24_P") (class "Default")
      (node (ref "P1") (pin "H28") (pinfunction "H28_H28") (pintype "passive"))
    )
    (net (code "212") (name "/LA25_N") (class "Default")
      (node (ref "P1") (pin "G28") (pinfunction "G28_G28") (pintype "passive"))
    )
    (net (code "213") (name "/LA25_P") (class "Default")
      (node (ref "P1") (pin "G27") (pinfunction "G27_G27") (pintype "passive"))
    )
    (net (code "214") (name "/LA26_N") (class "Default")
      (node (ref "P1") (pin "D27") (pinfunction "D27_D27") (pintype "passive"))
    )
    (net (code "215") (name "/LA26_P") (class "Default")
      (node (ref "P1") (pin "D26") (pinfunction "D26_D26") (pintype "passive"))
    )
    (net (code "216") (name "/LA27_N") (class "Default")
      (node (ref "P1") (pin "C27") (pinfunction "C27_C27") (pintype "passive"))
    )
    (net (code "217") (name "/LA27_P") (class "Default")
      (node (ref "P1") (pin "C26") (pinfunction "C26_C26") (pintype "passive"))
    )
    (net (code "218") (name "/LA28_N") (class "Default")
      (node (ref "P1") (pin "H32") (pinfunction "H32_H32") (pintype "passive"))
    )
    (net (code "219") (name "/LA28_P") (class "Default")
      (node (ref "P1") (pin "H31") (pinfunction "H31_H31") (pintype "passive"))
    )
    (net (code "220") (name "/LA29_N") (class "Default")
      (node (ref "P1") (pin "G31") (pinfunction "G31_G31") (pintype "passive"))
    )
    (net (code "221") (name "/LA29_P") (class "Default")
      (node (ref "P1") (pin "G30") (pinfunction "G30_G30") (pintype "passive"))
    )
    (net (code "222") (name "/LA30_N") (class "Default")
      (node (ref "P1") (pin "H35") (pinfunction "H35_H35") (pintype "passive"))
    )
    (net (code "223") (name "/LA30_P") (class "Default")
      (node (ref "P1") (pin "H34") (pinfunction "H34_H34") (pintype "passive"))
    )
    (net (code "224") (name "/LA31_N") (class "Default")
      (node (ref "P1") (pin "G34") (pinfunction "G34_G34") (pintype "passive"))
    )
    (net (code "225") (name "/LA31_P") (class "Default")
      (node (ref "P1") (pin "G33") (pinfunction "G33_G33") (pintype "passive"))
    )
    (net (code "226") (name "/LA32_N") (class "Default")
      (node (ref "P1") (pin "H38") (pinfunction "H38_H38") (pintype "passive"))
    )
    (net (code "227") (name "/LA32_P") (class "Default")
      (node (ref "P1") (pin "H37") (pinfunction "H37_H37") (pintype "passive"))
    )
    (net (code "228") (name "/LA33_N") (class "Default")
      (node (ref "P1") (pin "G37") (pinfunction "G37_G37") (pintype "passive"))
    )
    (net (code "229") (name "/LA33_P") (class "Default")
      (node (ref "P1") (pin "G36") (pinfunction "G36_G36") (pintype "passive"))
    )
    (net (code "231") (name "/PG_C2M") (class "Default")
      (node (ref "P1") (pin "D1") (pinfunction "D1_D1") (pintype "passive"))
    )
    (net (code "232") (name "/PG_M2C") (class "Default")
      (node (ref "P1") (pin "F1") (pinfunction "F1_F1") (pintype "passive"))
    )
    (net (code "233") (name "/PRSNT_M2C_L") (class "Default")
      (node (ref "P1") (pin "H2") (pinfunction "H2_H2") (pintype "passive"))
    )
    (net (code "234") (name "/SCL") (class "Default")
      (node (ref "P1") (pin "C30") (pinfunction "C30_C30") (pintype "passive"))
    )
    (net (code "235") (name "/SDA") (class "Default")
      (node (ref "P1") (pin "C31") (pinfunction "C31_C31") (pintype "passive"))
    )
    (net (code "236") (name "/TCK") (class "Default")
      (node (ref "P1") (pin "D29") (pinfunction "D29_D29") (pintype "passive"))
    )
    (net (code "237") (name "/TDI") (class "Default")
      (node (ref "P1") (pin "D30") (pinfunction "D30_D30") (pintype "passive"))
    )
    (net (code "238") (name "/TDO") (class "Default")
      (node (ref "P1") (pin "D31") (pinfunction "D31_D31") (pintype "passive"))
    )
    (net (code "239") (name "/TMS") (class "Default")
      (node (ref "P1") (pin "D33") (pinfunction "D33_D33") (pintype "passive"))
    )
    (net (code "240") (name "/TRST_L") (class "Default")
      (node (ref "P1") (pin "D34") (pinfunction "D34_D34") (pintype "passive"))
    )
    (net (code "241") (name "/VADJ") (class "Default")
      (node (ref "P1") (pin "E39") (pinfunction "E39_E39") (pintype "passive"))
      (node (ref "P1") (pin "F40") (pinfunction "F40_F40") (pintype "passive"))
      (node (ref "P1") (pin "G39") (pinfunction "G39_G39") (pintype "passive"))
      (node (ref "P1") (pin "H40") (pinfunction "H40_H40") (pintype "passive"))
    )
    (net (code "242") (name "/VIO_B_M2C") (class "Default")
      (node (ref "P1") (pin "J39") (pinfunction "J39_J39") (pintype "passive"))
      (node (ref "P1") (pin "K40") (pinfunction "K40_K40") (pintype "passive"))
    )
    (net (code "243") (name "/VREF_A_M2C") (class "Default")
      (node (ref "P1") (pin "H1") (pinfunction "H1_H1") (pintype "passive"))
    )
    (net (code "244") (name "/VREF_B_M2C") (class "Default")
      (node (ref "P1") (pin "K1") (pinfunction "K1_K1") (pintype "passive"))
    )
    (net (code "255") (name "unconnected-(P1-PadB20)") (class "Default")
      (node (ref "P1") (pin "B20") (pinfunction "B20_B20") (pintype "passive"))
    )
    (net (code "256") (name "unconnected-(P1-PadB21)") (class "Default")
      (node (ref "P1") (pin "B21") (pinfunction "B21_B21") (pintype "passive"))
    )
    (net (code "257") (name "unconnected-(P1-PadB40)") (class "Default")
      (node (ref "P1") (pin "B40") (pinfunction "B40_B40") (pintype "passive+no_connect"))
    )
  )
)
